# aux_board.net
KiCad netlist of a schematic drawn in EAGLE
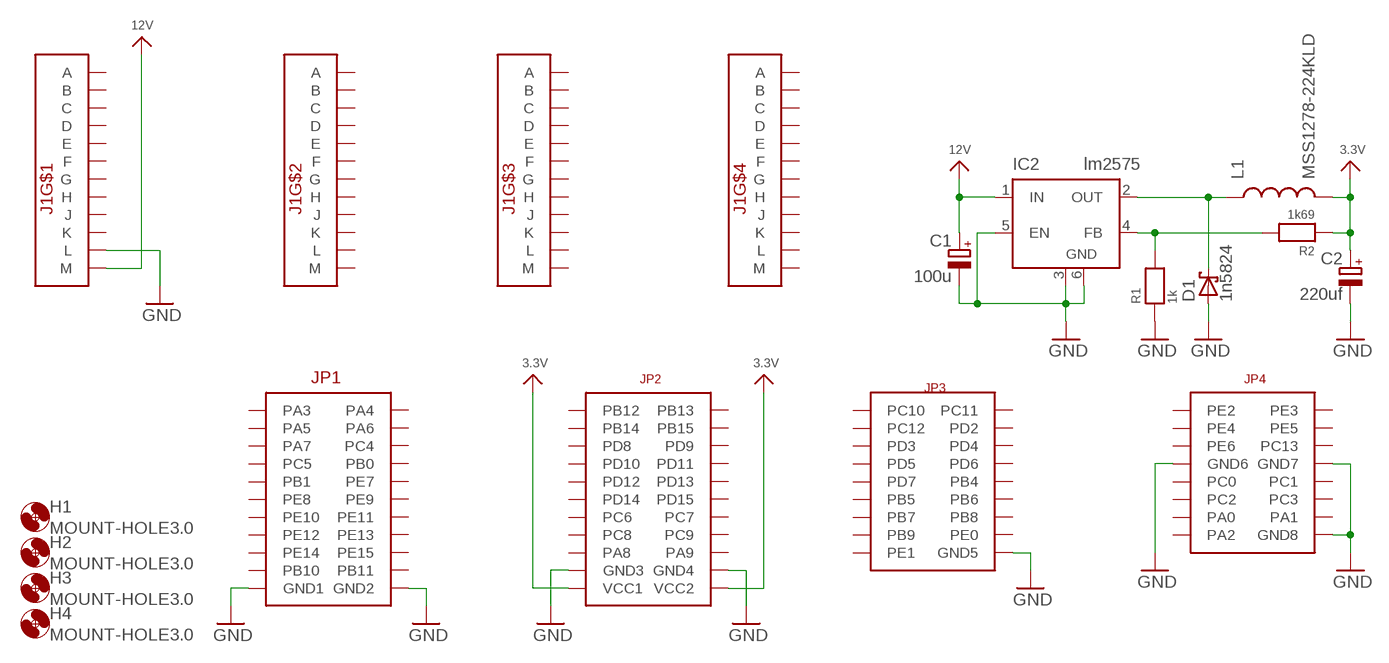
[diagram p0: schematic, sheet 1]

(export (version "E")
  (design (tool "Eeschema 10.0.6"))
  (components
    (comp (ref "C1")
      (value "100u")
      (footprint "eagle-import:E2,5-7")
      (libsource (lib "eagle-import") (part "CPOL-EUE2.5-7"))
    )
    (comp (ref "C2")
      (value "220uf")
      (footprint "eagle-import:E3,5-8")
      (libsource (lib "eagle-import") (part "CPOL-EUE3.5-8"))
    )
    (comp (ref "D1")
      (value "1n5824")
      (footprint "eagle-import:F126Z12")
      (libsource (lib "eagle-import") (part "SCHOTTKY-DIODEF126Z12"))
    )
    (comp (ref "H1")
      (value "MOUNT-HOLE3.0")
      (footprint "eagle-import:3,0")
      (libsource (lib "eagle-import") (part "MOUNT-HOLE3.0"))
    )
    (comp (ref "H2")
      (value "MOUNT-HOLE3.0")
      (footprint "eagle-import:3,0")
      (libsource (lib "eagle-import") (part "MOUNT-HOLE3.0"))
    )
    (comp (ref "H3")
      (value "MOUNT-HOLE3.0")
      (footprint "eagle-import:3,0")
      (libsource (lib "eagle-import") (part "MOUNT-HOLE3.0"))
    )
    (comp (ref "H4")
      (value "MOUNT-HOLE3.0")
      (footprint "eagle-import:3,0")
      (libsource (lib "eagle-import") (part "MOUNT-HOLE3.0"))
    )
    (comp (ref "IC2")
      (value "lm2575")
      (footprint "eagle-import:TO263-5")
      (libsource (lib "eagle-import") (part "LM2596S"))
    )
    (comp (ref "J1")
      (value "AUTOCONNECTOR")
      (footprint "eagle-import:AUTOCONNECTOR")
      (libsource (lib "eagle-import") (part "AUTOCONNECTOR"))
    )
    (comp (ref "L1")
      (value "MSS1278-224KLD")
      (footprint "eagle-import:CDRH125")
      (libsource (lib "eagle-import") (part "INDUCTORPWR"))
    )
    (comp (ref "R1")
      (value "1k")
      (footprint "eagle-import:_0603")
      (libsource (lib "eagle-import") (part "RESISTOR_0603"))
    )
    (comp (ref "R2")
      (value "1k69")
      (footprint "eagle-import:_0603")
      (libsource (lib "eagle-import") (part "RESISTOR_0603"))
    )
    (comp (ref "U$1")
      (value "CPU-BOARD")
      (footprint "eagle-import:CPU-BOARD-JP1")
      (libsource (lib "eagle-import") (part "CPU-BOARD"))
    )
  )
  (nets
    (net (code "1") (name "3.3V") (class "Default")
      (node (ref "C2") (pin "+") (pinfunction "+_+") (pintype "passive"))
      (node (ref "L1") (pin "2") (pinfunction "2_2") (pintype "passive"))
      (node (ref "R2") (pin "1") (pinfunction "1_1") (pintype "passive"))
      (node (ref "U$1") (pin "P$43") (pinfunction "VCC1_P$43") (pintype "bidirectional"))
      (node (ref "U$1") (pin "P$44") (pinfunction "VCC2_P$44") (pintype "bidirectional"))
    )
    (net (code "2") (name "12V") (class "Default")
      (node (ref "C1") (pin "+") (pinfunction "+_+") (pintype "passive"))
      (node (ref "IC2") (pin "1") (pinfunction "IN_1") (pintype "input"))
      (node (ref "J1") (pin "M1") (pinfunction "M_M1") (pintype "bidirectional"))
    )
    (net (code "3") (name "GND") (class "Default")
      (node (ref "C1") (pin "-") (pinfunction "-_-") (pintype "passive"))
      (node (ref "C2") (pin "-") (pinfunction "-_-") (pintype "passive"))
      (node (ref "D1") (pin "A") (pinfunction "A_A") (pintype "passive"))
      (node (ref "IC2") (pin "3") (pinfunction "GND_3") (pintype "power_in"))
      (node (ref "IC2") (pin "5") (pinfunction "EN_5") (pintype "input"))
      (node (ref "IC2") (pin "6") (pinfunction "GND_6") (pintype "power_in"))
      (node (ref "J1") (pin "L1") (pinfunction "L_L1") (pintype "bidirectional"))
      (node (ref "R1") (pin "1") (pinfunction "1_1") (pintype "passive"))
      (node (ref "U$1") (pin "P$21") (pinfunction "GND1_P$21") (pintype "bidirectional"))
      (node (ref "U$1") (pin "P$22") (pinfunction "GND2_P$22") (pintype "bidirectional"))
      (node (ref "U$1") (pin "P$41") (pinfunction "GND3_P$41") (pintype "bidirectional"))
      (node (ref "U$1") (pin "P$42") (pinfunction "GND4_P$42") (pintype "bidirectional"))
      (node (ref "U$1") (pin "P$62") (pinfunction "GND5_P$62") (pintype "bidirectional"))
      (node (ref "U$1") (pin "P$69") (pinfunction "GND6_P$69") (pintype "bidirectional"))
      (node (ref "U$1") (pin "P$70") (pinfunction "GND7_P$70") (pintype "bidirectional"))
      (node (ref "U$1") (pin "P$78") (pinfunction "GND8_P$78") (pintype "bidirectional"))
    )
    (net (code "4") (name "Net-(IC2-FB)") (class "Default")
      (node (ref "IC2") (pin "4") (pinfunction "FB_4") (pintype "input"))
      (node (ref "R1") (pin "2") (pinfunction "2_2") (pintype "passive"))
      (node (ref "R2") (pin "2") (pinfunction "2_2") (pintype "passive"))
    )
    (net (code "5") (name "Net-(IC2-OUT)") (class "Default")
      (node (ref "D1") (pin "C") (pinfunction "C_C") (pintype "passive"))
      (node (ref "IC2") (pin "2") (pinfunction "OUT_2") (pintype "output"))
      (node (ref "L1") (pin "1") (pinfunction "1_1") (pintype "passive"))
    )
    (net (code "6") (name "unconnected-(J1A-A-PadA1)") (class "Default")
      (node (ref "J1") (pin "A1") (pinfunction "A_A1") (pintype "bidirectional"))
    )
    (net (code "7") (name "unconnected-(J1A-B-PadB1)") (class "Default")
      (node (ref "J1") (pin "B1") (pinfunction "B_B1") (pintype "bidirectional"))
    )
    (net (code "8") (name "unconnected-(J1A-C-PadC1)") (class "Default")
      (node (ref "J1") (pin "C1") (pinfunction "C_C1") (pintype "bidirectional"))
    )
    (net (code "9") (name "unconnected-(J1A-D-PadD1)") (class "Default")
      (node (ref "J1") (pin "D1") (pinfunction "D_D1") (pintype "bidirectional"))
    )
    (net (code "10") (name "unconnected-(J1A-E-PadE1)") (class "Default")
      (node (ref "J1") (pin "E1") (pinfunction "E_E1") (pintype "bidirectional"))
    )
    (net (code "11") (name "unconnected-(J1A-F-PadF1)") (class "Default")
      (node (ref "J1") (pin "F1") (pinfunction "F_F1") (pintype "bidirectional"))
    )
    (net (code "12") (name "unconnected-(J1A-G-PadG1)") (class "Default")
      (node (ref "J1") (pin "G1") (pinfunction "G_G1") (pintype "bidirectional"))
    )
    (net (code "13") (name "unconnected-(J1A-H-PadH1)") (class "Default")
      (node (ref "J1") (pin "H1") (pinfunction "H_H1") (pintype "bidirectional"))
    )
    (net (code "14") (name "unconnected-(J1A-J-PadJ1)") (class "Default")
      (node (ref "J1") (pin "J1") (pinfunction "J_J1") (pintype "bidirectional"))
    )
    (net (code "15") (name "unconnected-(J1A-K-PadK1)") (class "Default")
      (node (ref "J1") (pin "K1") (pinfunction "K_K1") (pintype "bidirectional"))
    )
    (net (code "16") (name "unconnected-(J1B-A-PadA2)") (class "Default")
      (node (ref "J1") (pin "A2") (pinfunction "A_A2") (pintype "bidirectional"))
    )
    (net (code "17") (name "unconnected-(J1B-B-PadB2)") (class "Default")
      (node (ref "J1") (pin "B2") (pinfunction "B_B2") (pintype "bidirectional"))
    )
    (net (code "18") (name "unconnected-(J1B-C-PadC2)") (class "Default")
      (node (ref "J1") (pin "C2") (pinfunction "C_C2") (pintype "bidirectional"))
    )
    (net (code "19") (name "unconnected-(J1B-D-PadD2)") (class "Default")
      (node (ref "J1") (pin "D2") (pinfunction "D_D2") (pintype "bidirectional"))
    )
    (net (code "20") (name "unconnected-(J1B-E-PadE2)") (class "Default")
      (node (ref "J1") (pin "E2") (pinfunction "E_E2") (pintype "bidirectional"))
    )
    (net (code "21") (name "unconnected-(J1B-F-PadF2)") (class "Default")
      (node (ref "J1") (pin "F2") (pinfunction "F_F2") (pintype "bidirectional"))
    )
    (net (code "22") (name "unconnected-(J1B-G-PadG2)") (class "Default")
      (node (ref "J1") (pin "G2") (pinfunction "G_G2") (pintype "bidirectional"))
    )
    (net (code "23") (name "unconnected-(J1B-H-PadH2)") (class "Default")
      (node (ref "J1") (pin "H2") (pinfunction "H_H2") (pintype "bidirectional"))
    )
    (net (code "24") (name "unconnected-(J1B-J-PadJ2)") (class "Default")
      (node (ref "J1") (pin "J2") (pinfunction "J_J2") (pintype "bidirectional"))
    )
    (net (code "25") (name "unconnected-(J1B-K-PadK2)") (class "Default")
      (node (ref "J1") (pin "K2") (pinfunction "K_K2") (pintype "bidirectional"))
    )
    (net (code "26") (name "unconnected-(J1B-L-PadL2)") (class "Default")
      (node (ref "J1") (pin "L2") (pinfunction "L_L2") (pintype "bidirectional"))
    )
    (net (code "27") (name "unconnected-(J1B-M-PadM2)") (class "Default")
      (node (ref "J1") (pin "M2") (pinfunction "M_M2") (pintype "bidirectional"))
    )
    (net (code "28") (name "unconnected-(J1C-A-PadA3)") (class "Default")
      (node (ref "J1") (pin "A3") (pinfunction "A_A3") (pintype "bidirectional"))
    )
    (net (code "29") (name "unconnected-(J1C-B-PadB3)") (class "Default")
      (node (ref "J1") (pin "B3") (pinfunction "B_B3") (pintype "bidirectional"))
    )
    (net (code "30") (name "unconnected-(J1C-C-PadC3)") (class "Default")
      (node (ref "J1") (pin "C3") (pinfunction "C_C3") (pintype "bidirectional"))
    )
    (net (code "31") (name "unconnected-(J1C-D-PadD3)") (class "Default")
      (node (ref "J1") (pin "D3") (pinfunction "D_D3") (pintype "bidirectional"))
    )
    (net (code "32") (name "unconnected-(J1C-E-PadE3)") (class "Default")
      (node (ref "J1") (pin "E3") (pinfunction "E_E3") (pintype "bidirectional"))
    )
    (net (code "33") (name "unconnected-(J1C-F-PadF3)") (class "Default")
      (node (ref "J1") (pin "F3") (pinfunction "F_F3") (pintype "bidirectional"))
    )
    (net (code "34") (name "unconnected-(J1C-G-PadG3)") (class "Default")
      (node (ref "J1") (pin "G3") (pinfunction "G_G3") (pintype "bidirectional"))
    )
    (net (code "35") (name "unconnected-(J1C-H-PadH3)") (class "Default")
      (node (ref "J1") (pin "H3") (pinfunction "H_H3") (pintype "bidirectional"))
    )
    (net (code "36") (name "unconnected-(J1C-J-PadJ3)") (class "Default")
      (node (ref "J1") (pin "J3") (pinfunction "J_J3") (pintype "bidirectional"))
    )
    (net (code "37") (name "unconnected-(J1C-K-PadK3)") (class "Default")
      (node (ref "J1") (pin "K3") (pinfunction "K_K3") (pintype "bidirectional"))
    )
    (net (code "38") (name "unconnected-(J1C-L-PadL3)") (class "Default")
      (node (ref "J1") (pin "L3") (pinfunction "L_L3") (pintype "bidirectional"))
    )
    (net (code "39") (name "unconnected-(J1C-M-PadM3)") (class "Default")
      (node (ref "J1") (pin "M3") (pinfunction "M_M3") (pintype "bidirectional"))
    )
    (net (code "40") (name "unconnected-(J1D-A-PadA4)") (class "Default")
      (node (ref "J1") (pin "A4") (pinfunction "A_A4") (pintype "bidirectional"))
    )
    (net (code "41") (name "unconnected-(J1D-B-PadB4)") (class "Default")
      (node (ref "J1") (pin "B4") (pinfunction "B_B4") (pintype "bidirectional"))
    )
    (net (code "42") (name "unconnected-(J1D-C-PadC4)") (class "Default")
      (node (ref "J1") (pin "C4") (pinfunction "C_C4") (pintype "bidirectional"))
    )
    (net (code "43") (name "unconnected-(J1D-D-PadD4)") (class "Default")
      (node (ref "J1") (pin "D4") (pinfunction "D_D4") (pintype "bidirectional"))
    )
    (net (code "44") (name "unconnected-(J1D-E-PadE4)") (class "Default")
      (node (ref "J1") (pin "E4") (pinfunction "E_E4") (pintype "bidirectional"))
    )
    (net (code "45") (name "unconnected-(J1D-F-PadF4)") (class "Default")
      (node (ref "J1") (pin "F4") (pinfunction "F_F4") (pintype "bidirectional"))
    )
    (net (code "46") (name "unconnected-(J1D-G-PadG4)") (class "Default")
      (node (ref "J1") (pin "G4") (pinfunction "G_G4") (pintype "bidirectional"))
    )
    (net (code "47") (name "unconnected-(J1D-H-PadH4)") (class "Default")
      (node (ref "J1") (pin "H4") (pinfunction "H_H4") (pintype "bidirectional"))
    )
    (net (code "48") (name "unconnected-(J1D-J-PadJ4)") (class "Default")
      (node (ref "J1") (pin "J4") (pinfunction "J_J4") (pintype "bidirectional"))
    )
    (net (code "49") (name "unconnected-(J1D-K-PadK4)") (class "Default")
      (node (ref "J1") (pin "K4") (pinfunction "K_K4") (pintype "bidirectional"))
    )
    (net (code "50") (name "unconnected-(J1D-L-PadL4)") (class "Default")
      (node (ref "J1") (pin "L4") (pinfunction "L_L4") (pintype "bidirectional"))
    )
    (net (code "51") (name "unconnected-(J1D-M-PadM4)") (class "Default")
      (node (ref "J1") (pin "M4") (pinfunction "M_M4") (pintype "bidirectional"))
    )
    (net (code "52") (name "unconnected-(U$1A-PA3-PadP$1)") (class "Default")
      (node (ref "U$1") (pin "P$1") (pinfunction "PA3_P$1") (pintype "bidirectional"))
    )
    (net (code "53") (name "unconnected-(U$1A-PA4-PadP$2)") (class "Default")
      (node (ref "U$1") (pin "P$2") (pinfunction "PA4_P$2") (pintype "bidirectional"))
    )
    (net (code "54") (name "unconnected-(U$1A-PA5-PadP$3)") (class "Default")
      (node (ref "U$1") (pin "P$3") (pinfunction "PA5_P$3") (pintype "bidirectional"))
    )
    (net (code "55") (name "unconnected-(U$1A-PA6-PadP$4)") (class "Default")
      (node (ref "U$1") (pin "P$4") (pinfunction "PA6_P$4") (pintype "bidirectional"))
    )
    (net (code "56") (name "unconnected-(U$1A-PA7-PadP$5)") (class "Default")
      (node (ref "U$1") (pin "P$5") (pinfunction "PA7_P$5") (pintype "bidirectional"))
    )
    (net (code "57") (name "unconnected-(U$1A-PB0-PadP$8)") (class "Default")
      (node (ref "U$1") (pin "P$8") (pinfunction "PB0_P$8") (pintype "bidirectional"))
    )
    (net (code "58") (name "unconnected-(U$1A-PB1-PadP$9)") (class "Default")
      (node (ref "U$1") (pin "P$9") (pinfunction "PB1_P$9") (pintype "bidirectional"))
    )
    (net (code "59") (name "unconnected-(U$1A-PB10-PadP$19)") (class "Default")
      (node (ref "U$1") (pin "P$19") (pinfunction "PB10_P$19") (pintype "bidirectional"))
    )
    (net (code "60") (name "unconnected-(U$1A-PB11-PadP$20)") (class "Default")
      (node (ref "U$1") (pin "P$20") (pinfunction "PB11_P$20") (pintype "bidirectional"))
    )
    (net (code "61") (name "unconnected-(U$1A-PC4-PadP$6)") (class "Default")
      (node (ref "U$1") (pin "P$6") (pinfunction "PC4_P$6") (pintype "bidirectional"))
    )
    (net (code "62") (name "unconnected-(U$1A-PC5-PadP$7)") (class "Default")
      (node (ref "U$1") (pin "P$7") (pinfunction "PC5_P$7") (pintype "bidirectional"))
    )
    (net (code "63") (name "unconnected-(U$1A-PE7-PadP$10)") (class "Default")
      (node (ref "U$1") (pin "P$10") (pinfunction "PE7_P$10") (pintype "bidirectional"))
    )
    (net (code "64") (name "unconnected-(U$1A-PE8-PadP$11)") (class "Default")
      (node (ref "U$1") (pin "P$11") (pinfunction "PE8_P$11") (pintype "bidirectional"))
    )
    (net (code "65") (name "unconnected-(U$1A-PE9-PadP$12)") (class "Default")
      (node (ref "U$1") (pin "P$12") (pinfunction "PE9_P$12") (pintype "bidirectional"))
    )
    (net (code "66") (name "unconnected-(U$1A-PE10-PadP$13)") (class "Default")
      (node (ref "U$1") (pin "P$13") (pinfunction "PE10_P$13") (pintype "bidirectional"))
    )
    (net (code "67") (name "unconnected-(U$1A-PE11-PadP$14)") (class "Default")
      (node (ref "U$1") (pin "P$14") (pinfunction "PE11_P$14") (pintype "bidirectional"))
    )
    (net (code "68") (name "unconnected-(U$1A-PE12-PadP$15)") (class "Default")
      (node (ref "U$1") (pin "P$15") (pinfunction "PE12_P$15") (pintype "bidirectional"))
    )
    (net (code "69") (name "unconnected-(U$1A-PE13-PadP$16)") (class "Default")
      (node (ref "U$1") (pin "P$16") (pinfunction "PE13_P$16") (pintype "bidirectional"))
    )
    (net (code "70") (name "unconnected-(U$1A-PE14-PadP$17)") (class "Default")
      (node (ref "U$1") (pin "P$17") (pinfunction "PE14_P$17") (pintype "bidirectional"))
    )
    (net (code "71") (name "unconnected-(U$1A-PE15-PadP$18)") (class "Default")
      (node (ref "U$1") (pin "P$18") (pinfunction "PE15_P$18") (pintype "bidirectional"))
    )
    (net (code "72") (name "unconnected-(U$1B-PA8-PadP$39)") (class "Default")
      (node (ref "U$1") (pin "P$39") (pinfunction "PA8_P$39") (pintype "bidirectional"))
    )
    (net (code "73") (name "unconnected-(U$1B-PA9-PadP$40)") (class "Default")
      (node (ref "U$1") (pin "P$40") (pinfunction "PA9_P$40") (pintype "bidirectional"))
    )
    (net (code "74") (name "unconnected-(U$1B-PB12-PadP$23)") (class "Default")
      (node (ref "U$1") (pin "P$23") (pinfunction "PB12_P$23") (pintype "bidirectional"))
    )
    (net (code "75") (name "unconnected-(U$1B-PB13-PadP$24)") (class "Default")
      (node (ref "U$1") (pin "P$24") (pinfunction "PB13_P$24") (pintype "bidirectional"))
    )
    (net (code "76") (name "unconnected-(U$1B-PB14-PadP$25)") (class "Default")
      (node (ref "U$1") (pin "P$25") (pinfunction "PB14_P$25") (pintype "bidirectional"))
    )
    (net (code "77") (name "unconnected-(U$1B-PB15-PadP$26)") (class "Default")
      (node (ref "U$1") (pin "P$26") (pinfunction "PB15_P$26") (pintype "bidirectional"))
    )
    (net (code "78") (name "unconnected-(U$1B-PC6-PadP$35)") (class "Default")
      (node (ref "U$1") (pin "P$35") (pinfunction "PC6_P$35") (pintype "bidirectional"))
    )
    (net (code "79") (name "unconnected-(U$1B-PC7-PadP$36)") (class "Default")
      (node (ref "U$1") (pin "P$36") (pinfunction "PC7_P$36") (pintype "bidirectional"))
    )
    (net (code "80") (name "unconnected-(U$1B-PC8-PadP$37)") (class "Default")
      (node (ref "U$1") (pin "P$37") (pinfunction "PC8_P$37") (pintype "bidirectional"))
    )
    (net (code "81") (name "unconnected-(U$1B-PC9-PadP$38)") (class "Default")
      (node (ref "U$1") (pin "P$38") (pinfunction "PC9_P$38") (pintype "bidirectional"))
    )
    (net (code "82") (name "unconnected-(U$1B-PD8-PadP$27)") (class "Default")
      (node (ref "U$1") (pin "P$27") (pinfunction "PD8_P$27") (pintype "bidirectional"))
    )
    (net (code "83") (name "unconnected-(U$1B-PD9-PadP$28)") (class "Default")
      (node (ref "U$1") (pin "P$28") (pinfunction "PD9_P$28") (pintype "bidirectional"))
    )
    (net (code "84") (name "unconnected-(U$1B-PD10-PadP$29)") (class "Default")
      (node (ref "U$1") (pin "P$29") (pinfunction "PD10_P$29") (pintype "bidirectional"))
    )
    (net (code "85") (name "unconnected-(U$1B-PD11-PadP$30)") (class "Default")
      (node (ref "U$1") (pin "P$30") (pinfunction "PD11_P$30") (pintype "bidirectional"))
    )
    (net (code "86") (name "unconnected-(U$1B-PD12-PadP$31)") (class "Default")
      (node (ref "U$1") (pin "P$31") (pinfunction "PD12_P$31") (pintype "bidirectional"))
    )
    (net (code "87") (name "unconnected-(U$1B-PD13-PadP$32)") (class "Default")
      (node (ref "U$1") (pin "P$32") (pinfunction "PD13_P$32") (pintype "bidirectional"))
    )
    (net (code "88") (name "unconnected-(U$1B-PD14-PadP$33)") (class "Default")
      (node (ref "U$1") (pin "P$33") (pinfunction "PD14_P$33") (pintype "bidirectional"))
    )
    (net (code "89") (name "unconnected-(U$1B-PD15-PadP$34)") (class "Default")
      (node (ref "U$1") (pin "P$34") (pinfunction "PD15_P$34") (pintype "bidirectional"))
    )
    (net (code "90") (name "unconnected-(U$1C-PB4-PadP$54)") (class "Default")
      (node (ref "U$1") (pin "P$54") (pinfunction "PB4_P$54") (pintype "bidirectional"))
    )
    (net (code "91") (name "unconnected-(U$1C-PB5-PadP$55)") (class "Default")
      (node (ref "U$1") (pin "P$55") (pinfunction "PB5_P$55") (pintype "bidirectional"))
    )
    (net (code "92") (name "unconnected-(U$1C-PB6-PadP$56)") (class "Default")
      (node (ref "U$1") (pin "P$56") (pinfunction "PB6_P$56") (pintype "bidirectional"))
    )
    (net (code "93") (name "unconnected-(U$1C-PB7-PadP$57)") (class "Default")
      (node (ref "U$1") (pin "P$57") (pinfunction "PB7_P$57") (pintype "bidirectional"))
    )
    (net (code "94") (name "unconnected-(U$1C-PB8-PadP$58)") (class "Default")
      (node (ref "U$1") (pin "P$58") (pinfunction "PB8_P$58") (pintype "bidirectional"))
    )
    (net (code "95") (name "unconnected-(U$1C-PB9-PadP$59)") (class "Default")
      (node (ref "U$1") (pin "P$59") (pinfunction "PB9_P$59") (pintype "bidirectional"))
    )
    (net (code "96") (name "unconnected-(U$1C-PC10-PadP$45)") (class "Default")
      (node (ref "U$1") (pin "P$45") (pinfunction "PC10_P$45") (pintype "bidirectional"))
    )
    (net (code "97") (name "unconnected-(U$1C-PC11-PadP$46)") (class "Default")
      (node (ref "U$1") (pin "P$46") (pinfunction "PC11_P$46") (pintype "bidirectional"))
    )
    (net (code "98") (name "unconnected-(U$1C-PC12-PadP$47)") (class "Default")
      (node (ref "U$1") (pin "P$47") (pinfunction "PC12_P$47") (pintype "bidirectional"))
    )
    (net (code "99") (name "unconnected-(U$1C-PD2-PadP$48)") (class "Default")
      (node (ref "U$1") (pin "P$48") (pinfunction "PD2_P$48") (pintype "bidirectional"))
    )
    (net (code "100") (name "unconnected-(U$1C-PD3-PadP$49)") (class "Default")
      (node (ref "U$1") (pin "P$49") (pinfunction "PD3_P$49") (pintype "bidirectional"))
    )
    (net (code "101") (name "unconnected-(U$1C-PD4-PadP$50)") (class "Default")
      (node (ref "U$1") (pin "P$50") (pinfunction "PD4_P$50") (pintype "bidirectional"))
    )
    (net (code "102") (name "unconnected-(U$1C-PD5-PadP$51)") (class "Default")
      (node (ref "U$1") (pin "P$51") (pinfunction "PD5_P$51") (pintype "bidirectional"))
    )
    (net (code "103") (name "unconnected-(U$1C-PD6-PadP$52)") (class "Default")
      (node (ref "U$1") (pin "P$52") (pinfunction "PD6_P$52") (pintype "bidirectional"))
    )
    (net (code "104") (name "unconnected-(U$1C-PD7-PadP$53)") (class "Default")
      (node (ref "U$1") (pin "P$53") (pinfunction "PD7_P$53") (pintype "bidirectional"))
    )
    (net (code "105") (name "unconnected-(U$1C-PE0-PadP$60)") (class "Default")
      (node (ref "U$1") (pin "P$60") (pinfunction "PE0_P$60") (pintype "bidirectional"))
    )
    (net (code "106") (name "unconnected-(U$1C-PE1-PadP$61)") (class "Default")
      (node (ref "U$1") (pin "P$61") (pinfunction "PE1_P$61") (pintype "bidirectional"))
    )
    (net (code "107") (name "unconnected-(U$1D-PA0-PadP$75)") (class "Default")
      (node (ref "U$1") (pin "P$75") (pinfunction "PA0_P$75") (pintype "bidirectional"))
    )
    (net (code "108") (name "unconnected-(U$1D-PA1-PadP$76)") (class "Default")
      (node (ref "U$1") (pin "P$76") (pinfunction "PA1_P$76") (pintype "bidirectional"))
    )
    (net (code "109") (name "unconnected-(U$1D-PA2-PadP$77)") (class "Default")
      (node (ref "U$1") (pin "P$77") (pinfunction "PA2_P$77") (pintype "bidirectional"))
    )
    (net (code "110") (name "unconnected-(U$1D-PC0-PadP$71)") (class "Default")
      (node (ref "U$1") (pin "P$71") (pinfunction "PC0_P$71") (pintype "bidirectional"))
    )
    (net (code "111") (name "unconnected-(U$1D-PC1-PadP$72)") (class "Default")
      (node (ref "U$1") (pin "P$72") (pinfunction "PC1_P$72") (pintype "bidirectional"))
    )
    (net (code "112") (name "unconnected-(U$1D-PC2-PadP$73)") (class "Default")
      (node (ref "U$1") (pin "P$73") (pinfunction "PC2_P$73") (pintype "bidirectional"))
    )
    (net (code "113") (name "unconnected-(U$1D-PC3-PadP$74)") (class "Default")
      (node (ref "U$1") (pin "P$74") (pinfunction "PC3_P$74") (pintype "bidirectional"))
    )
    (net (code "114") (name "unconnected-(U$1D-PC13-PadP$68)") (class "Default")
      (node (ref "U$1") (pin "P$68") (pinfunction "PC13_P$68") (pintype "bidirectional"))
    )
    (net (code "115") (name "unconnected-(U$1D-PE2-PadP$63)") (class "Default")
      (node (ref "U$1") (pin "P$63") (pinfunction "PE2_P$63") (pintype "bidirectional"))
    )
    (net (code "116") (name "unconnected-(U$1D-PE3-PadP$64)") (class "Default")
      (node (ref "U$1") (pin "P$64") (pinfunction "PE3_P$64") (pintype "bidirectional"))
    )
    (net (code "117") (name "unconnected-(U$1D-PE4-PadP$65)") (class "Default")
      (node (ref "U$1") (pin "P$65") (pinfunction "PE4_P$65") (pintype "bidirectional"))
    )
    (net (code "118") (name "unconnected-(U$1D-PE5-PadP$66)") (class "Default")
      (node (ref "U$1") (pin "P$66") (pinfunction "PE5_P$66") (pintype "bidirectional"))
    )
    (net (code "119") (name "unconnected-(U$1D-PE6-PadP$67)") (class "Default")
      (node (ref "U$1") (pin "P$67") (pinfunction "PE6_P$67") (pintype "bidirectional"))
    )
  )
)
